# Wireless_Estop.net
KiCad netlist of a schematic drawn in EAGLE
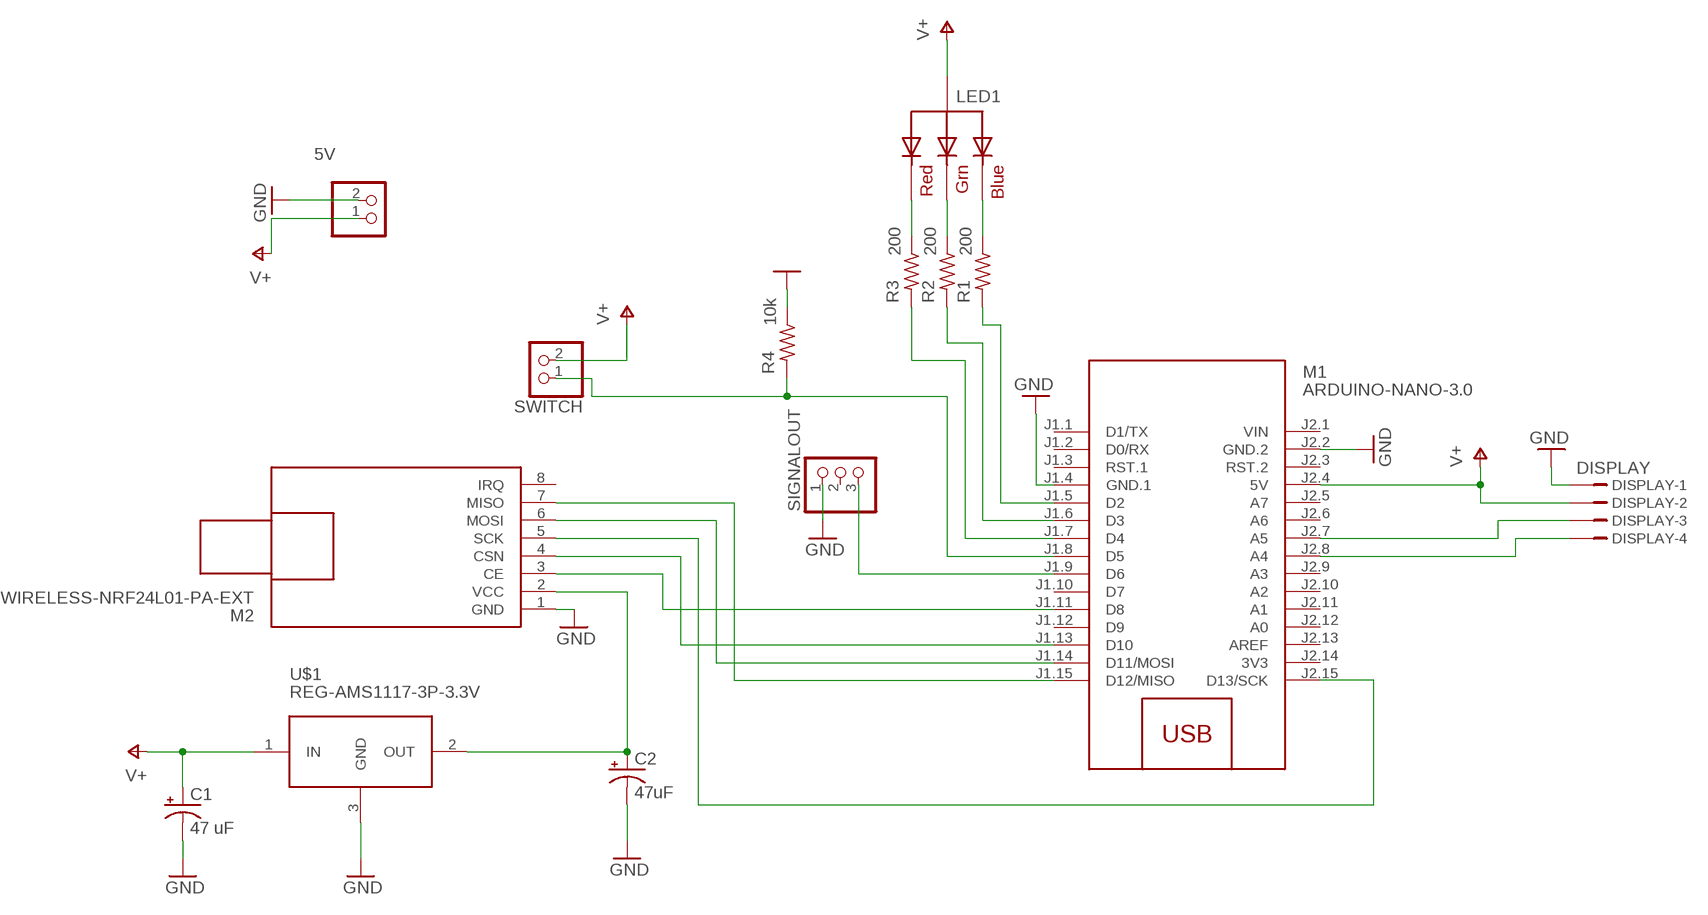
[diagram p0: schematic, sheet 1]

(export (version "E")
  (design (tool "Eeschema 10.0.6"))
  (components
    (comp (ref "5V")
      (value "JST_2PIN-THM")
      (footprint "eagle-import:JST-PH-2-THM")
      (libsource (lib "eagle-import") (part "JST_2PIN-THM"))
    )
    (comp (ref "C1")
      (value "47 uF")
      (footprint "eagle-import:E2,5-5")
      (libsource (lib "eagle-import") (part "CPOL-USE2.5-5"))
    )
    (comp (ref "C2")
      (value "47uF")
      (footprint "eagle-import:E2,5-5")
      (libsource (lib "eagle-import") (part "CPOL-USE2.5-5"))
    )
    (comp (ref "DISPLAY")
      (value "DISPLAY")
      (footprint "eagle-import:B4B-ZR")
      (fields (field (name "MF") "FARNELL") (field (name "MPN") "B4B-ZR(LF)(SN)"))
      (libsource (lib "eagle-import") (part "?4B-ZRB"))
    )
    (comp (ref "LED1")
      (value "RGBLED_CA-5MM")
      (footprint "eagle-import:LED5MMRGB")
      (libsource (lib "eagle-import") (part "RGBLED_CA-5MM"))
    )
    (comp (ref "M1")
      (value "ARDUINO-NANO-3.0")
      (footprint "eagle-import:ARDUINO-NANO-3.0")
      (libsource (lib "eagle-import") (part "ARDUINO-NANO-3.0"))
    )
    (comp (ref "M2")
      (value "WIRELESS-NRF24L01-PA-EXT")
      (footprint "eagle-import:WIRELESS-NRF24L01-PA-EXT")
      (libsource (lib "eagle-import") (part "WIRELESS-NRF24L01-PA-EXT"))
    )
    (comp (ref "R1")
      (value "200")
      (footprint "eagle-import:0805-THM")
      (libsource (lib "eagle-import") (part "FLIPFLOP-RES"))
    )
    (comp (ref "R2")
      (value "200")
      (footprint "eagle-import:0805-THM")
      (libsource (lib "eagle-import") (part "FLIPFLOP-RES"))
    )
    (comp (ref "R3")
      (value "200")
      (footprint "eagle-import:0805-THM")
      (libsource (lib "eagle-import") (part "FLIPFLOP-RES"))
    )
    (comp (ref "R4")
      (value "10k")
      (footprint "eagle-import:0805-THM")
      (libsource (lib "eagle-import") (part "FLIPFLOP-RES"))
    )
    (comp (ref "SIGNALOUT")
      (value "PINHD-1X3")
      (footprint "eagle-import:1X03")
      (libsource (lib "eagle-import") (part "PINHD-1X3"))
    )
    (comp (ref "SWITCH")
      (value "PINHD-1X2")
      (footprint "eagle-import:1X02")
      (libsource (lib "eagle-import") (part "PINHD-1X2"))
    )
    (comp (ref "U$1")
      (value "REG-AMS1117-3P-3.3V")
      (footprint "eagle-import:REG-AMS1117-3P")
      (libsource (lib "eagle-import") (part "REG-AMS1117-3P-3.3V"))
    )
  )
  (nets
    (net (code "1") (name "/3V3") (class "Default")
      (node (ref "M1") (pin "J2.14") (pinfunction "3V3_J2.14") (pintype "power_in"))
    )
    (net (code "2") (name "/VIN") (class "Default")
      (node (ref "M1") (pin "J2.1") (pinfunction "VIN_J2.1") (pintype "power_in"))
    )
    (net (code "3") (name "GND") (class "Default")
      (node (ref "5V") (pin "2") (pinfunction "1_2") (pintype "passive"))
      (node (ref "C1") (pin "-") (pinfunction "-_-") (pintype "passive"))
      (node (ref "C2") (pin "-") (pinfunction "-_-") (pintype "passive"))
      (node (ref "DISPLAY") (pin "1") (pinfunction "1_1") (pintype "passive"))
      (node (ref "M1") (pin "J1.4") (pinfunction "GND.1_J1.4") (pintype "power_in"))
      (node (ref "M1") (pin "J2.2") (pinfunction "GND.2_J2.2") (pintype "power_in"))
      (node (ref "M2") (pin "1") (pinfunction "GND_1") (pintype "power_in"))
      (node (ref "R4") (pin "1") (pinfunction "1_1") (pintype "passive"))
      (node (ref "SIGNALOUT") (pin "1") (pinfunction "1_1") (pintype "passive"))
      (node (ref "U$1") (pin "3") (pinfunction "GND_3") (pintype "bidirectional"))
    )
    (net (code "4") (name "Net-(DISPLAYC-1)") (class "Default")
      (node (ref "DISPLAY") (pin "3") (pinfunction "1_3") (pintype "passive"))
      (node (ref "M1") (pin "J2.7") (pinfunction "A5_J2.7") (pintype "bidirectional"))
    )
    (net (code "5") (name "Net-(DISPLAYD-1)") (class "Default")
      (node (ref "DISPLAY") (pin "4") (pinfunction "1_4") (pintype "passive"))
      (node (ref "M1") (pin "J2.8") (pinfunction "A4_J2.8") (pintype "bidirectional"))
    )
    (net (code "6") (name "Net-(LED1-BLUE)") (class "Default")
      (node (ref "LED1") (pin "4") (pinfunction "BLUE_4") (pintype "bidirectional"))
      (node (ref "R1") (pin "1") (pinfunction "1_1") (pintype "passive"))
    )
    (net (code "7") (name "Net-(LED1-GREEN)") (class "Default")
      (node (ref "LED1") (pin "3") (pinfunction "GREEN_3") (pintype "bidirectional"))
      (node (ref "R2") (pin "1") (pinfunction "1_1") (pintype "passive"))
    )
    (net (code "8") (name "Net-(LED1-RED)") (class "Default")
      (node (ref "LED1") (pin "1") (pinfunction "RED_1") (pintype "bidirectional"))
      (node (ref "R3") (pin "1") (pinfunction "1_1") (pintype "passive"))
    )
    (net (code "9") (name "Net-(M1-D2)") (class "Default")
      (node (ref "M1") (pin "J1.5") (pinfunction "D2_J1.5") (pintype "bidirectional"))
      (node (ref "R1") (pin "2") (pinfunction "2_2") (pintype "passive"))
    )
    (net (code "10") (name "Net-(M1-D3)") (class "Default")
      (node (ref "M1") (pin "J1.6") (pinfunction "D3_J1.6") (pintype "bidirectional"))
      (node (ref "R2") (pin "2") (pinfunction "2_2") (pintype "passive"))
    )
    (net (code "11") (name "Net-(M1-D4)") (class "Default")
      (node (ref "M1") (pin "J1.7") (pinfunction "D4_J1.7") (pintype "bidirectional"))
      (node (ref "R3") (pin "2") (pinfunction "2_2") (pintype "passive"))
    )
    (net (code "12") (name "Net-(M1-D5)") (class "Default")
      (node (ref "M1") (pin "J1.8") (pinfunction "D5_J1.8") (pintype "bidirectional"))
      (node (ref "R4") (pin "2") (pinfunction "2_2") (pintype "passive"))
      (node (ref "SWITCH") (pin "1") (pinfunction "1_1") (pintype "passive"))
    )
    (net (code "13") (name "Net-(M1-D6)") (class "Default")
      (node (ref "M1") (pin "J1.9") (pinfunction "D6_J1.9") (pintype "bidirectional"))
      (node (ref "SIGNALOUT") (pin "3") (pinfunction "3_3") (pintype "passive"))
    )
    (net (code "14") (name "Net-(M1-D8)") (class "Default")
      (node (ref "M1") (pin "J1.11") (pinfunction "D8_J1.11") (pintype "bidirectional"))
      (node (ref "M2") (pin "3") (pinfunction "CE_3") (pintype "bidirectional"))
    )
    (net (code "15") (name "Net-(M1-D10)") (class "Default")
      (node (ref "M1") (pin "J1.13") (pinfunction "D10_J1.13") (pintype "bidirectional"))
      (node (ref "M2") (pin "4") (pinfunction "CSN_4") (pintype "bidirectional"))
    )
    (net (code "16") (name "Net-(M1-D11{slash}MOSI)") (class "Default")
      (node (ref "M1") (pin "J1.14") (pinfunction "D11/MOSI_J1.14") (pintype "bidirectional"))
      (node (ref "M2") (pin "6") (pinfunction "MOSI_6") (pintype "bidirectional"))
    )
    (net (code "17") (name "Net-(M1-D12{slash}MISO)") (class "Default")
      (node (ref "M1") (pin "J1.15") (pinfunction "D12/MISO_J1.15") (pintype "bidirectional"))
      (node (ref "M2") (pin "7") (pinfunction "MISO_7") (pintype "bidirectional"))
    )
    (net (code "18") (name "Net-(M1-D13{slash}SCK)") (class "Default")
      (node (ref "M1") (pin "J2.15") (pinfunction "D13/SCK_J2.15") (pintype "bidirectional"))
      (node (ref "M2") (pin "5") (pinfunction "SCK_5") (pintype "bidirectional"))
    )
    (net (code "19") (name "Net-(M2-VCC)") (class "Default")
      (node (ref "C2") (pin "+") (pinfunction "+_+") (pintype "passive"))
      (node (ref "M2") (pin "2") (pinfunction "VCC_2") (pintype "power_in"))
      (node (ref "U$1") (pin "2") (pinfunction "OUT_2") (pintype "bidirectional"))
    )
    (net (code "20") (name "V+") (class "Default")
      (node (ref "5V") (pin "1") (pinfunction "2_1") (pintype "passive"))
      (node (ref "C1") (pin "+") (pinfunction "+_+") (pintype "passive"))
      (node (ref "DISPLAY") (pin "2") (pinfunction "1_2") (pintype "passive"))
      (node (ref "LED1") (pin "2") (pinfunction "VCC_2") (pintype "bidirectional"))
      (node (ref "M1") (pin "J2.4") (pinfunction "5V_J2.4") (pintype "power_in"))
      (node (ref "SWITCH") (pin "2") (pinfunction "2_2") (pintype "passive"))
      (node (ref "U$1") (pin "1") (pinfunction "IN_1") (pintype "bidirectional"))
    )
    (net (code "21") (name "unconnected-(M1-A0-PadJ2.12)") (class "Default")
      (node (ref "M1") (pin "J2.12") (pinfunction "A0_J2.12") (pintype "bidirectional"))
    )
    (net (code "22") (name "unconnected-(M1-A1-PadJ2.11)") (class "Default")
      (node (ref "M1") (pin "J2.11") (pinfunction "A1_J2.11") (pintype "bidirectional"))
    )
    (net (code "23") (name "unconnected-(M1-A2-PadJ2.10)") (class "Default")
      (node (ref "M1") (pin "J2.10") (pinfunction "A2_J2.10") (pintype "bidirectional"))
    )
    (net (code "24") (name "unconnected-(M1-A3-PadJ2.9)") (class "Default")
      (node (ref "M1") (pin "J2.9") (pinfunction "A3_J2.9") (pintype "bidirectional"))
    )
    (net (code "25") (name "unconnected-(M1-A6-PadJ2.6)") (class "Default")
      (node (ref "M1") (pin "J2.6") (pinfunction "A6_J2.6") (pintype "bidirectional"))
    )
    (net (code "26") (name "unconnected-(M1-A7-PadJ2.5)") (class "Default")
      (node (ref "M1") (pin "J2.5") (pinfunction "A7_J2.5") (pintype "bidirectional"))
    )
    (net (code "27") (name "unconnected-(M1-AREF-PadJ2.13)") (class "Default")
      (node (ref "M1") (pin "J2.13") (pinfunction "AREF_J2.13") (pintype "bidirectional"))
    )
    (net (code "28") (name "unconnected-(M1-D0{slash}RX-PadJ1.2)") (class "Default")
      (node (ref "M1") (pin "J1.2") (pinfunction "D0/RX_J1.2") (pintype "bidirectional"))
    )
    (net (code "29") (name "unconnected-(M1-D1{slash}TX-PadJ1.1)") (class "Default")
      (node (ref "M1") (pin "J1.1") (pinfunction "D1/TX_J1.1") (pintype "bidirectional"))
    )
    (net (code "30") (name "unconnected-(M1-D7-PadJ1.10)") (class "Default")
      (node (ref "M1") (pin "J1.10") (pinfunction "D7_J1.10") (pintype "bidirectional"))
    )
    (net (code "31") (name "unconnected-(M1-D9-PadJ1.12)") (class "Default")
      (node (ref "M1") (pin "J1.12") (pinfunction "D9_J1.12") (pintype "bidirectional"))
    )
    (net (code "32") (name "unconnected-(M1-RST.1-PadJ1.3)") (class "Default")
      (node (ref "M1") (pin "J1.3") (pinfunction "RST.1_J1.3") (pintype "bidirectional"))
    )
    (net (code "33") (name "unconnected-(M1-RST.2-PadJ2.3)") (class "Default")
      (node (ref "M1") (pin "J2.3") (pinfunction "RST.2_J2.3") (pintype "bidirectional"))
    )
    (net (code "34") (name "unconnected-(M2-IRQ-Pad8)") (class "Default")
      (node (ref "M2") (pin "8") (pinfunction "IRQ_8") (pintype "bidirectional"))
    )
    (net (code "35") (name "unconnected-(SIGNALOUT-Pad2)") (class "Default")
      (node (ref "SIGNALOUT") (pin "2") (pinfunction "2_2") (pintype "passive"))
    )
  )
)
